# analog_channel3.net
KiCad netlist of a schematic drawn in Altium Designer
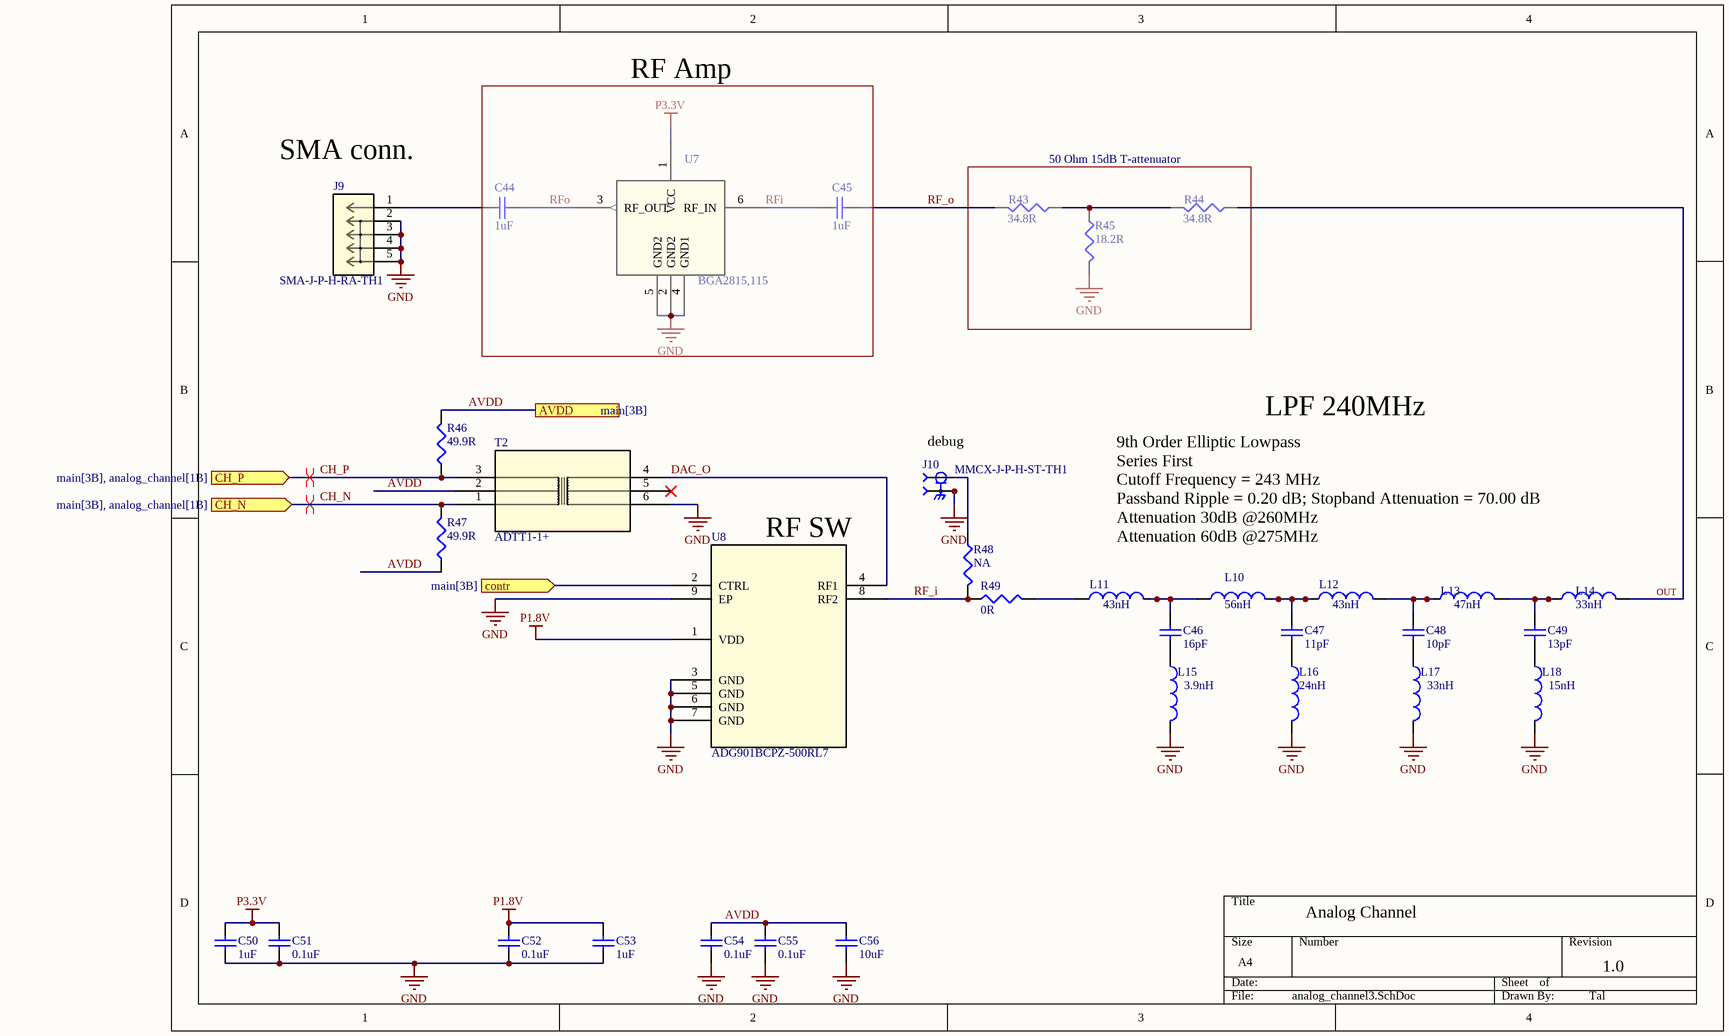
[diagram p0: analog_channel3.SchDoc]

(export (version "E")
  (design (tool "Eeschema 10.0.6"))
  (components
    (comp (ref "C44")
      (value "1uF 25V")
      (footprint "c0402")
      (description "CAP CER 1uF 25V X5R 0402")
      (fields
        (field (name "MANUFACTURER PART NUMBER") "C1005C0G1H6R8D")
        (field (name "MANUFACTURER") "TDK Corporation")
        (field (name "CAPACITANCE") "1uF")
      )
      (libsource (lib "L_SCH_C") (part "CAP CER 6.8pF 50V NP0 0402"))
    )
    (comp (ref "C45")
      (value "1uF 25V")
      (footprint "c0402")
      (description "CAP CER 1uF 25V X5R 0402")
      (fields
        (field (name "MANUFACTURER PART NUMBER") "C1005C0G1H6R8D")
        (field (name "MANUFACTURER") "TDK Corporation")
        (field (name "CAPACITANCE") "1uF")
      )
      (libsource (lib "L_SCH_C") (part "CAP CER 6.8pF 50V NP0 0402"))
    )
    (comp (ref "C46")
      (value "16pF 50V")
      (footprint "c0402")
      (description "CAP CER 16PF 50V 5% NP0 0402")
      (fields
        (field (name "MANUFACTURER") "TDK Corporation")
        (field (name "MANUFACTURER PART NUMBER") "C1005C0G1H200J")
        (field (name "CAPACITANCE") "16pF")
      )
      (libsource (lib "L_SCH_C") (part "CAP CER 20pF 50V 5% NP0 0402"))
    )
    (comp (ref "C47")
      (value "11pF 50V")
      (footprint "c0402")
      (description "CAP CER 11PF 50V 5% NP0 0402")
      (fields
        (field (name "MANUFACTURER") "TDK Corporation")
        (field (name "MANUFACTURER PART NUMBER") "C1005C0G1H200J")
        (field (name "CAPACITANCE") "11pF")
      )
      (libsource (lib "L_SCH_C") (part "CAP CER 20pF 50V 5% NP0 0402"))
    )
    (comp (ref "C48")
      (value "10pF 50V")
      (footprint "c0402")
      (description "CAP CER 10PF 50V 5% NP0 0402")
      (fields
        (field (name "MANUFACTURER") "TDK Corporation")
        (field (name "MANUFACTURER PART NUMBER") "C1005C0G1H200J")
        (field (name "CAPACITANCE") "10pF")
      )
      (libsource (lib "L_SCH_C") (part "CAP CER 20pF 50V 5% NP0 0402"))
    )
    (comp (ref "C49")
      (value "13pF 50V")
      (footprint "c0402")
      (description "CAP CER 13PF 50V 5% NP0 0402")
      (fields
        (field (name "MANUFACTURER") "TDK Corporation")
        (field (name "MANUFACTURER PART NUMBER") "C1005C0G1H200J")
        (field (name "CAPACITANCE") "13pF")
      )
      (libsource (lib "L_SCH_C") (part "CAP CER 20pF 50V 5% NP0 0402"))
    )
    (comp (ref "C50")
      (value "1uF 25V")
      (footprint "c0402")
      (description "CAP CER 1uF 25V X5R 0402")
      (fields
        (field (name "MANUFACTURER PART NUMBER") "C1005C0G1H6R8D")
        (field (name "MANUFACTURER") "TDK Corporation")
        (field (name "CAPACITANCE") "1uF")
      )
      (libsource (lib "L_SCH_C") (part "CAP CER 6.8pF 50V NP0 0402"))
    )
    (comp (ref "C51")
      (value "0.1uF 50V")
      (footprint "c0402")
      (description "CAP CER 0.1uF 50V NP0 0402")
      (fields
        (field (name "MANUFACTURER PART NUMBER") "C1005C0G1H6R8D")
        (field (name "MANUFACTURER") "TDK Corporation")
        (field (name "CAPACITANCE") "0.1uF")
      )
      (libsource (lib "L_SCH_C") (part "CAP CER 6.8pF 50V NP0 0402"))
    )
    (comp (ref "C52")
      (value "0.1uF 50V")
      (footprint "c0402")
      (description "CAP CER 0.1uF 50V NP0 0402")
      (fields
        (field (name "MANUFACTURER PART NUMBER") "C1005C0G1H6R8D")
        (field (name "MANUFACTURER") "TDK Corporation")
        (field (name "CAPACITANCE") "0.1uF")
      )
      (libsource (lib "L_SCH_C") (part "CAP CER 6.8pF 50V NP0 0402"))
    )
    (comp (ref "C53")
      (value "1uF 25V")
      (footprint "c0402")
      (description "CAP CER 1uF 25V X5R 0402")
      (fields
        (field (name "MANUFACTURER PART NUMBER") "C1005C0G1H6R8D")
        (field (name "MANUFACTURER") "TDK Corporation")
        (field (name "CAPACITANCE") "1uF")
      )
      (libsource (lib "L_SCH_C") (part "CAP CER 6.8pF 50V NP0 0402"))
    )
    (comp (ref "C54")
      (value "0.1uF 50V")
      (footprint "c0402")
      (description "CAP CER 0.1uF 50V NP0 0402")
      (fields
        (field (name "MANUFACTURER PART NUMBER") "C1005C0G1H6R8D")
        (field (name "MANUFACTURER") "TDK Corporation")
        (field (name "CAPACITANCE") "0.1uF")
      )
      (libsource (lib "L_SCH_C") (part "CAP CER 6.8pF 50V NP0 0402"))
    )
    (comp (ref "C55")
      (value "0.1uF 50V")
      (footprint "c0402")
      (description "CAP CER 0.1uF 50V NP0 0402")
      (fields
        (field (name "MANUFACTURER PART NUMBER") "C1005C0G1H6R8D")
        (field (name "MANUFACTURER") "TDK Corporation")
        (field (name "CAPACITANCE") "0.1uF")
      )
      (libsource (lib "L_SCH_C") (part "CAP CER 6.8pF 50V NP0 0402"))
    )
    (comp (ref "C56")
      (value "10uF 10V")
      (footprint "c0402")
      (description "CAP CER 10uF 10V X5R 0402")
      (fields
        (field (name "MANUFACTURER PART NUMBER") "C1005C0G1H6R8D")
        (field (name "MANUFACTURER") "TDK Corporation")
        (field (name "CAPACITANCE") "10uF")
      )
      (libsource (lib "L_SCH_C") (part "CAP CER 6.8pF 50V NP0 0402"))
    )
    (comp (ref "J9")
      (value "SMA-J-P-H-RA-TH1")
      (footprint "CONN_SMA-J-P-H-RA-TH1_SAI")
      (description "No Description Available")
      (fields (field (name "COPYRIGHT") "Copyright (C) 2023 Ultra Librarian. All rights reserved."))
      (libsource (lib "SMA-J-P-H-RA-TH1") (part "SMA-J-P-H-RA-TH1"))
    )
    (comp (ref "J10")
      (value "MMCX-J-P-H-ST-TH1")
      (footprint "SAMTEC_MMCX-J-P-H-ST-TH1")
      (description "MMCX STRAIGHT, THROUGH HOLE JACK- 50 OHM")
      (fields (field (name "MF") "Samtec"))
      (libsource (lib "MMCX-J-P-H-ST-TH1") (part "MMCX-J-P-H-ST-TH1"))
    )
    (comp (ref "L10")
      (value "56nH")
      (footprint "0402-A")
      (description "Inductor")
      (fields (field (name "PUBLISHER") "Altium Limited"))
      (libsource (lib "Miscellaneous Devices") (part "Inductor"))
    )
    (comp (ref "L11")
      (value "43nH")
      (footprint "0402-A")
      (description "Inductor")
      (fields (field (name "PUBLISHER") "Altium Limited"))
      (libsource (lib "Miscellaneous Devices") (part "Inductor"))
    )
    (comp (ref "L12")
      (value "43nH")
      (footprint "0402-A")
      (description "Inductor")
      (fields (field (name "PUBLISHER") "Altium Limited"))
      (libsource (lib "Miscellaneous Devices") (part "Inductor"))
    )
    (comp (ref "L13")
      (value "47nH")
      (footprint "0402-A")
      (description "Inductor")
      (fields (field (name "PUBLISHER") "Altium Limited"))
      (libsource (lib "Miscellaneous Devices") (part "Inductor"))
    )
    (comp (ref "L14")
      (value "33nH")
      (footprint "0402-A")
      (description "Inductor")
      (fields (field (name "PUBLISHER") "Altium Limited"))
      (libsource (lib "Miscellaneous Devices") (part "Inductor"))
    )
    (comp (ref "L15")
      (value "3.9nH")
      (footprint "0402-A")
      (description "Inductor")
      (fields (field (name "PUBLISHER") "Altium Limited"))
      (libsource (lib "Miscellaneous Devices") (part "Inductor"))
    )
    (comp (ref "L16")
      (value "24nH")
      (footprint "0402-A")
      (description "Inductor")
      (fields (field (name "PUBLISHER") "Altium Limited"))
      (libsource (lib "Miscellaneous Devices") (part "Inductor"))
    )
    (comp (ref "L17")
      (value "33nH")
      (footprint "0402-A")
      (description "Inductor")
      (fields (field (name "PUBLISHER") "Altium Limited"))
      (libsource (lib "Miscellaneous Devices") (part "Inductor"))
    )
    (comp (ref "L18")
      (value "15nH")
      (footprint "0402-A")
      (description "Inductor")
      (fields (field (name "PUBLISHER") "Altium Limited"))
      (libsource (lib "Miscellaneous Devices") (part "Inductor"))
    )
    (comp (ref "R43")
      (value "34.8R")
      (footprint "r0402")
      (description "RES 34.8 OHM 1/10W 1% 0402 SMD")
      (fields
        (field (name "MANUFACTURER PART NUMBER") "ERJ-2RKF1000X")
        (field (name "MANUFACTURER") "Panasonic Electronic Components")
      )
      (libsource (lib "L_SCH_R") (part "RES 100 OHM 1/10W 1% 0402 SMD"))
    )
    (comp (ref "R44")
      (value "34.8R")
      (footprint "r0402")
      (description "RES 34.8 OHM 1/10W 1% 0402 SMD")
      (fields
        (field (name "MANUFACTURER PART NUMBER") "ERJ-2RKF1000X")
        (field (name "MANUFACTURER") "Panasonic Electronic Components")
      )
      (libsource (lib "L_SCH_R") (part "RES 100 OHM 1/10W 1% 0402 SMD"))
    )
    (comp (ref "R45")
      (value "18.2R")
      (footprint "r0402")
      (description "RES 18.2 OHM 1/10W 1% 0402 SMD")
      (fields
        (field (name "MANUFACTURER PART NUMBER") "ERJ-2RKF1000X")
        (field (name "MANUFACTURER") "Panasonic Electronic Components")
      )
      (libsource (lib "L_SCH_R") (part "RES 100 OHM 1/10W 1% 0402 SMD"))
    )
    (comp (ref "R46")
      (value "49.9R")
      (footprint "r0402")
      (description "RES 49.9 OHM 1/10W 1% 0402 SMD")
      (fields
        (field (name "MANUFACTURER PART NUMBER") "ERJ-2RKF1000X")
        (field (name "MANUFACTURER") "Panasonic Electronic Components")
      )
      (libsource (lib "L_SCH_R") (part "RES 100 OHM 1/10W 1% 0402 SMD"))
    )
    (comp (ref "R47")
      (value "49.9R")
      (footprint "r0402")
      (description "RES 49.9 OHM 1/10W 1% 0402 SMD")
      (fields
        (field (name "MANUFACTURER PART NUMBER") "ERJ-2RKF1000X")
        (field (name "MANUFACTURER") "Panasonic Electronic Components")
      )
      (libsource (lib "L_SCH_R") (part "RES 100 OHM 1/10W 1% 0402 SMD"))
    )
    (comp (ref "R48")
      (value "NA")
      (footprint "r0402")
      (description "RES 0 OHM 1/10W 1% 0402 SMD")
      (fields
        (field (name "MANUFACTURER PART NUMBER") "ERJ-2RKF1000X")
        (field (name "MANUFACTURER") "Panasonic Electronic Components")
      )
      (libsource (lib "L_SCH_R") (part "RES 100 OHM 1/10W 1% 0402 SMD"))
    )
    (comp (ref "R49")
      (value "0R")
      (footprint "r0402")
      (description "RES 0 OHM 1/10W 1% 0402 SMD")
      (fields
        (field (name "MANUFACTURER PART NUMBER") "ERJ-2RKF1000X")
        (field (name "MANUFACTURER") "Panasonic Electronic Components")
      )
      (libsource (lib "L_SCH_R") (part "RES 100 OHM 1/10W 1% 0402 SMD"))
    )
    (comp (ref "T2")
      (value "ADTT1-1+")
      (footprint "CD542_MNC")
      (description "No Description Available")
      (fields (field (name "COPYRIGHT") "Copyright (C) 2023 Ultra Librarian. All rights reserved."))
      (libsource (lib "ADTT1-1&plus_") (part "ADTT1-1+"))
    )
    (comp (ref "U7")
      (value "BGA2815,115")
      (footprint "SOT_2815,115_NXP")
      (description "No Description Available")
      (fields (field (name "COPYRIGHT") "Copyright (C) 2023 Ultra Librarian. All rights reserved."))
      (libsource (lib "BGA2815,115") (part "BGA2815,115"))
    )
    (comp (ref "U8")
      (value "ADG901BCPZ-500RL7")
      (footprint "CP_8_2_ADI")
      (description "No Description Available")
      (fields (field (name "COPYRIGHT") "Copyright (C) 2023 Ultra Librarian. All rights reserved."))
      (libsource (lib "ADG901BCPZ-500RL7") (part "ADG901BCPZ-500RL7"))
    )
  )
  (nets
    (net (code "1") (name "/AVDD") (class "Default")
      (node (ref "C54") (pin "2") (pinfunction "2_2") (pintype "passive"))
      (node (ref "C55") (pin "2") (pinfunction "2_2") (pintype "passive"))
      (node (ref "C56") (pin "2") (pinfunction "2_2") (pintype "passive"))
      (node (ref "R46") (pin "2") (pinfunction "2_2") (pintype "passive"))
      (node (ref "R47") (pin "1") (pinfunction "1_1") (pintype "passive"))
      (node (ref "T2") (pin "2") (pinfunction "2_2") (pintype "passive"))
    )
    (net (code "2") (name "/CH_N") (class "Default")
      (node (ref "R47") (pin "2") (pinfunction "2_2") (pintype "passive"))
      (node (ref "T2") (pin "1") (pinfunction "1_1") (pintype "passive"))
    )
    (net (code "3") (name "/CH_P") (class "Default")
      (node (ref "R46") (pin "1") (pinfunction "1_1") (pintype "passive"))
      (node (ref "T2") (pin "3") (pinfunction "3_3") (pintype "passive"))
    )
    (net (code "4") (name "/DAC_O") (class "Default")
      (node (ref "T2") (pin "4") (pinfunction "4_4") (pintype "passive"))
      (node (ref "U8") (pin "4") (pinfunction "RF1_4") (pintype "passive"))
    )
    (net (code "5") (name "/OUT") (class "Default")
      (node (ref "L14") (pin "2") (pinfunction "2_2") (pintype "passive"))
      (node (ref "R44") (pin "1") (pinfunction "1_1") (pintype "passive"))
    )
    (net (code "6") (name "/RF_i") (class "Default")
      (node (ref "R48") (pin "2") (pinfunction "2_2") (pintype "passive"))
      (node (ref "R49") (pin "1") (pinfunction "1_1") (pintype "passive"))
      (node (ref "U8") (pin "8") (pinfunction "RF2_8") (pintype "passive"))
    )
    (net (code "7") (name "/RF_o") (class "Default")
      (node (ref "C45") (pin "2") (pinfunction "2_2") (pintype "passive"))
      (node (ref "R43") (pin "2") (pinfunction "2_2") (pintype "passive"))
    )
    (net (code "8") (name "/RFi") (class "Default")
      (node (ref "C45") (pin "1") (pinfunction "1_1") (pintype "passive"))
      (node (ref "U7") (pin "6") (pinfunction "RF_IN_6") (pintype "passive"))
    )
    (net (code "9") (name "/RFo") (class "Default")
      (node (ref "C44") (pin "2") (pinfunction "2_2") (pintype "passive"))
      (node (ref "U7") (pin "3") (pinfunction "RF_OUT_3") (pintype "output"))
    )
    (net (code "10") (name "/contr") (class "Default")
      (node (ref "U8") (pin "2") (pinfunction "CTRL_2") (pintype "passive"))
    )
    (net (code "11") (name "GND") (class "Default")
      (node (ref "C50") (pin "1") (pinfunction "1_1") (pintype "passive"))
      (node (ref "C51") (pin "1") (pinfunction "1_1") (pintype "passive"))
      (node (ref "C52") (pin "1") (pinfunction "1_1") (pintype "passive"))
      (node (ref "C53") (pin "1") (pinfunction "1_1") (pintype "passive"))
      (node (ref "C54") (pin "1") (pinfunction "1_1") (pintype "passive"))
      (node (ref "C55") (pin "1") (pinfunction "1_1") (pintype "passive"))
      (node (ref "C56") (pin "1") (pinfunction "1_1") (pintype "passive"))
      (node (ref "J10") (pin "S1") (pinfunction "2_S1") (pintype "passive"))
      (node (ref "J10") (pin "S2") (pinfunction "2_S2") (pintype "passive"))
      (node (ref "J10") (pin "S3") (pinfunction "2_S3") (pintype "passive"))
      (node (ref "J10") (pin "S4") (pinfunction "2_S4") (pintype "passive"))
      (node (ref "J9") (pin "2") (pinfunction "2_2") (pintype "passive"))
      (node (ref "J9") (pin "3") (pinfunction "3_3") (pintype "passive"))
      (node (ref "J9") (pin "4") (pinfunction "4_4") (pintype "passive"))
      (node (ref "J9") (pin "5") (pinfunction "5_5") (pintype "passive"))
      (node (ref "L15") (pin "2") (pinfunction "2_2") (pintype "passive"))
      (node (ref "L16") (pin "2") (pinfunction "2_2") (pintype "passive"))
      (node (ref "L17") (pin "2") (pinfunction "2_2") (pintype "passive"))
      (node (ref "L18") (pin "2") (pinfunction "2_2") (pintype "passive"))
      (node (ref "R45") (pin "2") (pinfunction "2_2") (pintype "passive"))
      (node (ref "T2") (pin "6") (pinfunction "6_6") (pintype "passive"))
      (node (ref "U7") (pin "2") (pinfunction "GND2_2") (pintype "passive"))
      (node (ref "U7") (pin "4") (pinfunction "GND1_4") (pintype "passive"))
      (node (ref "U7") (pin "5") (pinfunction "GND2_5") (pintype "passive"))
      (node (ref "U8") (pin "3") (pinfunction "GND_3") (pintype "passive"))
      (node (ref "U8") (pin "5") (pinfunction "GND_5") (pintype "passive"))
      (node (ref "U8") (pin "6") (pinfunction "GND_6") (pintype "passive"))
      (node (ref "U8") (pin "7") (pinfunction "GND_7") (pintype "passive"))
      (node (ref "U8") (pin "9") (pinfunction "EP_9") (pintype "passive"))
    )
    (net (code "12") (name "Net-(C44-Pad1)") (class "Default")
      (node (ref "C44") (pin "1") (pinfunction "1_1") (pintype "passive"))
      (node (ref "J9") (pin "1") (pinfunction "1_1") (pintype "passive"))
    )
    (net (code "13") (name "Net-(C46-Pad1)") (class "Default")
      (node (ref "C46") (pin "1") (pinfunction "1_1") (pintype "passive"))
      (node (ref "L10") (pin "1") (pinfunction "1_1") (pintype "passive"))
      (node (ref "L11") (pin "2") (pinfunction "2_2") (pintype "passive"))
    )
    (net (code "14") (name "Net-(C46-Pad2)") (class "Default")
      (node (ref "C46") (pin "2") (pinfunction "2_2") (pintype "passive"))
      (node (ref "L15") (pin "1") (pinfunction "1_1") (pintype "passive"))
    )
    (net (code "15") (name "Net-(C47-Pad1)") (class "Default")
      (node (ref "C47") (pin "1") (pinfunction "1_1") (pintype "passive"))
      (node (ref "L10") (pin "2") (pinfunction "2_2") (pintype "passive"))
      (node (ref "L12") (pin "1") (pinfunction "1_1") (pintype "passive"))
    )
    (net (code "16") (name "Net-(C47-Pad2)") (class "Default")
      (node (ref "C47") (pin "2") (pinfunction "2_2") (pintype "passive"))
      (node (ref "L16") (pin "1") (pinfunction "1_1") (pintype "passive"))
    )
    (net (code "17") (name "Net-(C48-Pad1)") (class "Default")
      (node (ref "C48") (pin "1") (pinfunction "1_1") (pintype "passive"))
      (node (ref "L12") (pin "2") (pinfunction "2_2") (pintype "passive"))
      (node (ref "L13") (pin "1") (pinfunction "1_1") (pintype "passive"))
    )
    (net (code "18") (name "Net-(C48-Pad2)") (class "Default")
      (node (ref "C48") (pin "2") (pinfunction "2_2") (pintype "passive"))
      (node (ref "L17") (pin "1") (pinfunction "1_1") (pintype "passive"))
    )
    (net (code "19") (name "Net-(C49-Pad1)") (class "Default")
      (node (ref "C49") (pin "1") (pinfunction "1_1") (pintype "passive"))
      (node (ref "L13") (pin "2") (pinfunction "2_2") (pintype "passive"))
      (node (ref "L14") (pin "1") (pinfunction "1_1") (pintype "passive"))
    )
    (net (code "20") (name "Net-(C49-Pad2)") (class "Default")
      (node (ref "C49") (pin "2") (pinfunction "2_2") (pintype "passive"))
      (node (ref "L18") (pin "1") (pinfunction "1_1") (pintype "passive"))
    )
    (net (code "21") (name "Net-(J10-Pad1)") (class "Default")
      (node (ref "J10") (pin "1") (pinfunction "1_1") (pintype "passive"))
      (node (ref "R48") (pin "1") (pinfunction "1_1") (pintype "passive"))
    )
    (net (code "22") (name "Net-(L11-Pad1)") (class "Default")
      (node (ref "L11") (pin "1") (pinfunction "1_1") (pintype "passive"))
      (node (ref "R49") (pin "2") (pinfunction "2_2") (pintype "passive"))
    )
    (net (code "23") (name "Net-(R43-Pad1)") (class "Default")
      (node (ref "R43") (pin "1") (pinfunction "1_1") (pintype "passive"))
      (node (ref "R44") (pin "2") (pinfunction "2_2") (pintype "passive"))
      (node (ref "R45") (pin "1") (pinfunction "1_1") (pintype "passive"))
    )
    (net (code "24") (name "P1.8V") (class "Default")
      (node (ref "C52") (pin "2") (pinfunction "2_2") (pintype "passive"))
      (node (ref "C53") (pin "2") (pinfunction "2_2") (pintype "passive"))
      (node (ref "U8") (pin "1") (pinfunction "VDD_1") (pintype "power_in"))
    )
    (net (code "25") (name "P3.3V") (class "Default")
      (node (ref "C50") (pin "2") (pinfunction "2_2") (pintype "passive"))
      (node (ref "C51") (pin "2") (pinfunction "2_2") (pintype "passive"))
      (node (ref "U7") (pin "1") (pinfunction "VCC_1") (pintype "power_in"))
    )
    (net (code "26") (name "unconnected-(T2-Pad5)") (class "Default")
      (node (ref "T2") (pin "5") (pinfunction "5_5") (pintype "passive+no_connect"))
    )
  )
)
